# MPL115A2-v12.net
KiCad netlist of a schematic drawn in EAGLE
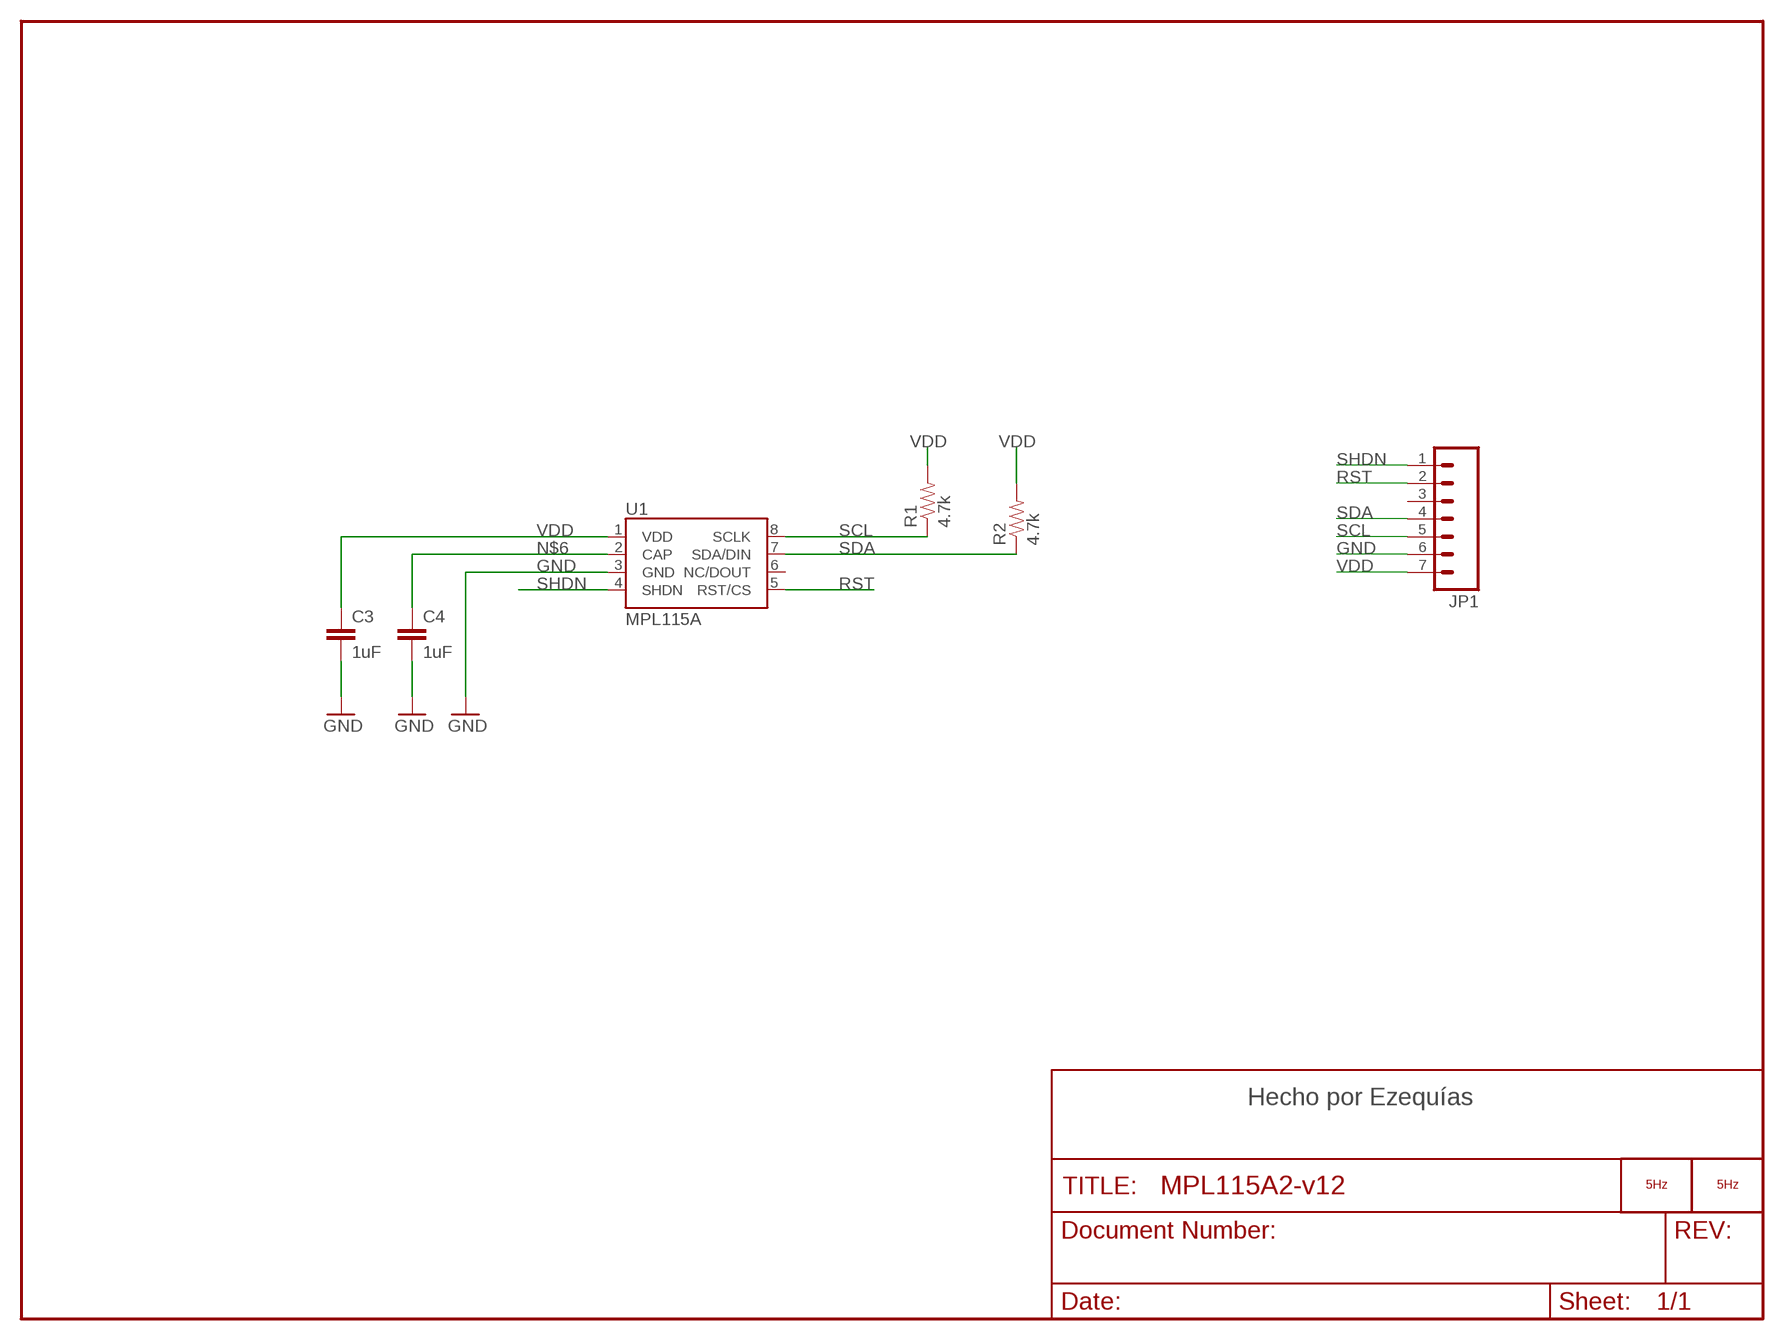
[diagram p0: schematic, sheet 1]

(export (version "E")
  (design (tool "Eeschema 10.0.6"))
  (components
    (comp (ref "C3")
      (value "1uF")
      (footprint "eagle-import:0805-CAP")
      (libsource (lib "eagle-import") (part "CAP0805-CAP"))
    )
    (comp (ref "C4")
      (value "1uF")
      (footprint "eagle-import:0805-CAP")
      (libsource (lib "eagle-import") (part "CAP0805-CAP"))
    )
    (comp (ref "JP1")
      (value "M07")
      (footprint "eagle-import:1X07")
      (libsource (lib "eagle-import") (part "M07"))
    )
    (comp (ref "LOGO1")
      (value "LOGO_5HZ_H_5MM")
      (footprint "eagle-import:5HZ_LOGO_H_5MM")
      (libsource (lib "eagle-import") (part "LOGO_5HZ_H_5MM"))
    )
    (comp (ref "LOGO2")
      (value "LOGO_5HZ_MINUSCULAS")
      (footprint "eagle-import:5HZ_LOGO_H_5MM")
      (libsource (lib "eagle-import") (part "LOGO_5HZ_H_5MM"))
    )
    (comp (ref "R1")
      (value "4.7k")
      (footprint "eagle-import:1_6W-RES")
      (libsource (lib "eagle-import") (part "RESISTORPTH-1/6W"))
    )
    (comp (ref "R2")
      (value "4.7k")
      (footprint "eagle-import:1_6W-RES")
      (libsource (lib "eagle-import") (part "RESISTORPTH-1/6W"))
    )
    (comp (ref "U1")
      (value "MPL115A")
      (footprint "eagle-import:LGA8")
      (libsource (lib "eagle-import") (part "MPL115A"))
    )
  )
  (nets
    (net (code "1") (name "/N$6") (class "Default")
      (node (ref "C4") (pin "1") (pinfunction "1_1") (pintype "passive"))
      (node (ref "U1") (pin "2") (pinfunction "CAP_2") (pintype "bidirectional"))
    )
    (net (code "2") (name "/RST") (class "Default")
      (node (ref "JP1") (pin "2") (pinfunction "2_2") (pintype "passive"))
      (node (ref "U1") (pin "5") (pinfunction "RST/CS_5") (pintype "bidirectional"))
    )
    (net (code "3") (name "/SCL") (class "Default")
      (node (ref "JP1") (pin "5") (pinfunction "5_5") (pintype "passive"))
      (node (ref "R1") (pin "1") (pinfunction "1_1") (pintype "passive"))
      (node (ref "U1") (pin "8") (pinfunction "SCLK_8") (pintype "bidirectional"))
    )
    (net (code "4") (name "/SDA") (class "Default")
      (node (ref "JP1") (pin "4") (pinfunction "4_4") (pintype "passive"))
      (node (ref "R2") (pin "1") (pinfunction "1_1") (pintype "passive"))
      (node (ref "U1") (pin "7") (pinfunction "SDA/DIN_7") (pintype "bidirectional"))
    )
    (net (code "5") (name "/SHDN") (class "Default")
      (node (ref "JP1") (pin "1") (pinfunction "1_1") (pintype "passive"))
      (node (ref "U1") (pin "4") (pinfunction "SHDN_4") (pintype "bidirectional"))
    )
    (net (code "6") (name "/VDD") (class "Default")
      (node (ref "C3") (pin "1") (pinfunction "1_1") (pintype "passive"))
      (node (ref "JP1") (pin "7") (pinfunction "7_7") (pintype "passive"))
      (node (ref "R1") (pin "2") (pinfunction "2_2") (pintype "passive"))
      (node (ref "R2") (pin "2") (pinfunction "2_2") (pintype "passive"))
      (node (ref "U1") (pin "1") (pinfunction "VDD_1") (pintype "bidirectional"))
    )
    (net (code "7") (name "GND") (class "Default")
      (node (ref "C3") (pin "2") (pinfunction "2_2") (pintype "passive"))
      (node (ref "C4") (pin "2") (pinfunction "2_2") (pintype "passive"))
      (node (ref "JP1") (pin "6") (pinfunction "6_6") (pintype "passive"))
      (node (ref "U1") (pin "3") (pinfunction "GND_3") (pintype "bidirectional"))
    )
    (net (code "8") (name "unconnected-(JP1-Pad3)") (class "Default")
      (node (ref "JP1") (pin "3") (pinfunction "3_3") (pintype "passive"))
    )
    (net (code "9") (name "unconnected-(U1-NC{slash}DOUT-Pad6)") (class "Default")
      (node (ref "U1") (pin "6") (pinfunction "NC/DOUT_6") (pintype "bidirectional"))
    )
  )
)
